# LPF_500Hz.net
KiCad netlist of a schematic drawn in Altium Designer
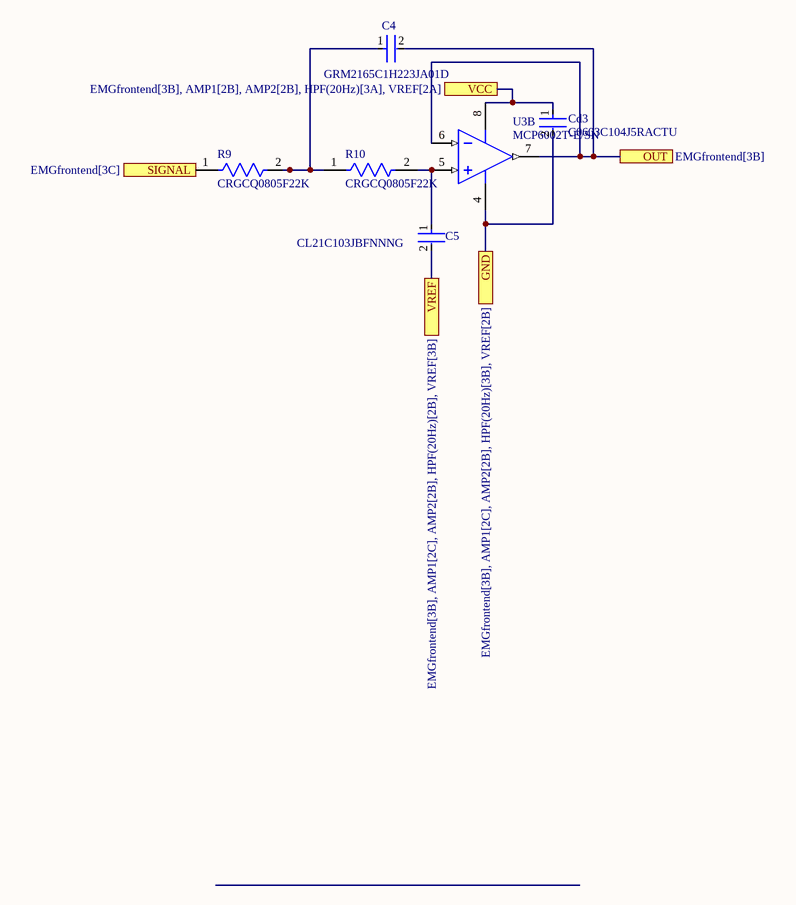
[diagram p0: LPF(500Hz).SchDoc]

(export (version "E")
  (design (tool "Eeschema 10.0.6"))
  (components
    (comp (ref "C4")
      (value "GRM2165C1H223JA01D")
      (footprint "FP-GRM216-0_1-0_05-MFG")
      (description "22000pF")
      (libsource (lib "Altium Content Vault") (part "b4654b650e69147ec39a6b967a45e02"))
    )
    (comp (ref "C5")
      (value "CL21C103JBFNNNG")
      (footprint "FP-CL21-IPC_B")
      (description "10nF")
      (fields (field (name "TOLERANCE") "5%") (field (name "VOLTAGE") "50V"))
      (libsource (lib "Altium Content Vault") (part "b4654b650e69147ec39a6b967a45e02"))
    )
    (comp (ref "Cd3")
      (value "C0603C104J5RACTU")
      (footprint "FP-C0603C-CF-MFG")
      (description "CAP CER 0.1UF 50V 5% X7R 0603")
      (fields
        (field (name "TOLERANCE") "0.05")
        (field (name "OCTOPART") "https://octopart.com/c0603c104j5ractu-kemet-10440638")
      )
      (libsource (lib "Altium Content Vault") (part "b4654b650e69147ec39a6b967a45e02"))
    )
    (comp (ref "R9")
      (value "CRGCQ0805F22K")
      (footprint "FP-CRGCQ0805-IPC_C")
      (description "CRGCQ0805 22KΩ 0.125W ±100ppm/°C 1% 150V")
      (fields
        (field (name "OCTOPART") "https://octopart.com/crgcq0805f22k-te+connectivity-91018161")
        (field (name "MANUFACTURER") "TE Connectivity")
      )
      (libsource (lib "Altium Content Vault") (part "1029c3af85768c4190bb7ad29bc67b5"))
    )
    (comp (ref "R10")
      (value "CRGCQ0805F22K")
      (footprint "FP-CRGCQ0805-IPC_C")
      (description "CRGCQ0805 22KΩ 0.125W ±100ppm/°C 1% 150V")
      (fields
        (field (name "OCTOPART") "https://octopart.com/crgcq0805f22k-te+connectivity-91018161")
        (field (name "MANUFACTURER") "TE Connectivity")
      )
      (libsource (lib "Altium Content Vault") (part "1029c3af85768c4190bb7ad29bc67b5"))
    )
    (comp (ref "U3")
      (value "MCP6002T-E/SN")
      (footprint "SOIC-SN8_N")
      (description "None")
      (libsource (lib "Altium Content Vault") (part "AMP-OPA-MCP6002-IL8"))
    )
  )
  (nets
    (net (code "1") (name "/GND") (class "Default")
      (node (ref "Cd3") (pin "2") (pinfunction "2_2") (pintype "passive"))
      (node (ref "U3") (pin "4") (pinfunction "VSS_4") (pintype "power_in"))
    )
    (net (code "2") (name "/OUT") (class "Default")
      (node (ref "C4") (pin "2") (pinfunction "2_2") (pintype "passive"))
      (node (ref "U3") (pin "6") (pinfunction "VINB-_6") (pintype "input"))
      (node (ref "U3") (pin "7") (pinfunction "VOUTB_7") (pintype "output"))
    )
    (net (code "3") (name "/SIGNAL") (class "Default")
      (node (ref "R9") (pin "1") (pinfunction "1_1") (pintype "passive"))
    )
    (net (code "4") (name "/VCC") (class "Default")
      (node (ref "Cd3") (pin "1") (pinfunction "1_1") (pintype "passive"))
      (node (ref "U3") (pin "8") (pinfunction "VDD_8") (pintype "power_in"))
    )
    (net (code "5") (name "/VREF") (class "Default")
      (node (ref "C5") (pin "2") (pinfunction "2_2") (pintype "passive"))
    )
    (net (code "6") (name "Net-(C4-Pad1)") (class "Default")
      (node (ref "C4") (pin "1") (pinfunction "1_1") (pintype "passive"))
      (node (ref "R10") (pin "1") (pinfunction "1_1") (pintype "passive"))
      (node (ref "R9") (pin "2") (pinfunction "2_2") (pintype "passive"))
    )
    (net (code "7") (name "Net-(U3B-VINB+)") (class "Default")
      (node (ref "C5") (pin "1") (pinfunction "1_1") (pintype "passive"))
      (node (ref "R10") (pin "2") (pinfunction "2_2") (pintype "passive"))
      (node (ref "U3") (pin "5") (pinfunction "VINB+_5") (pintype "input"))
    )
  )
)
